# compass.net
KiCad netlist of a schematic drawn in EAGLE
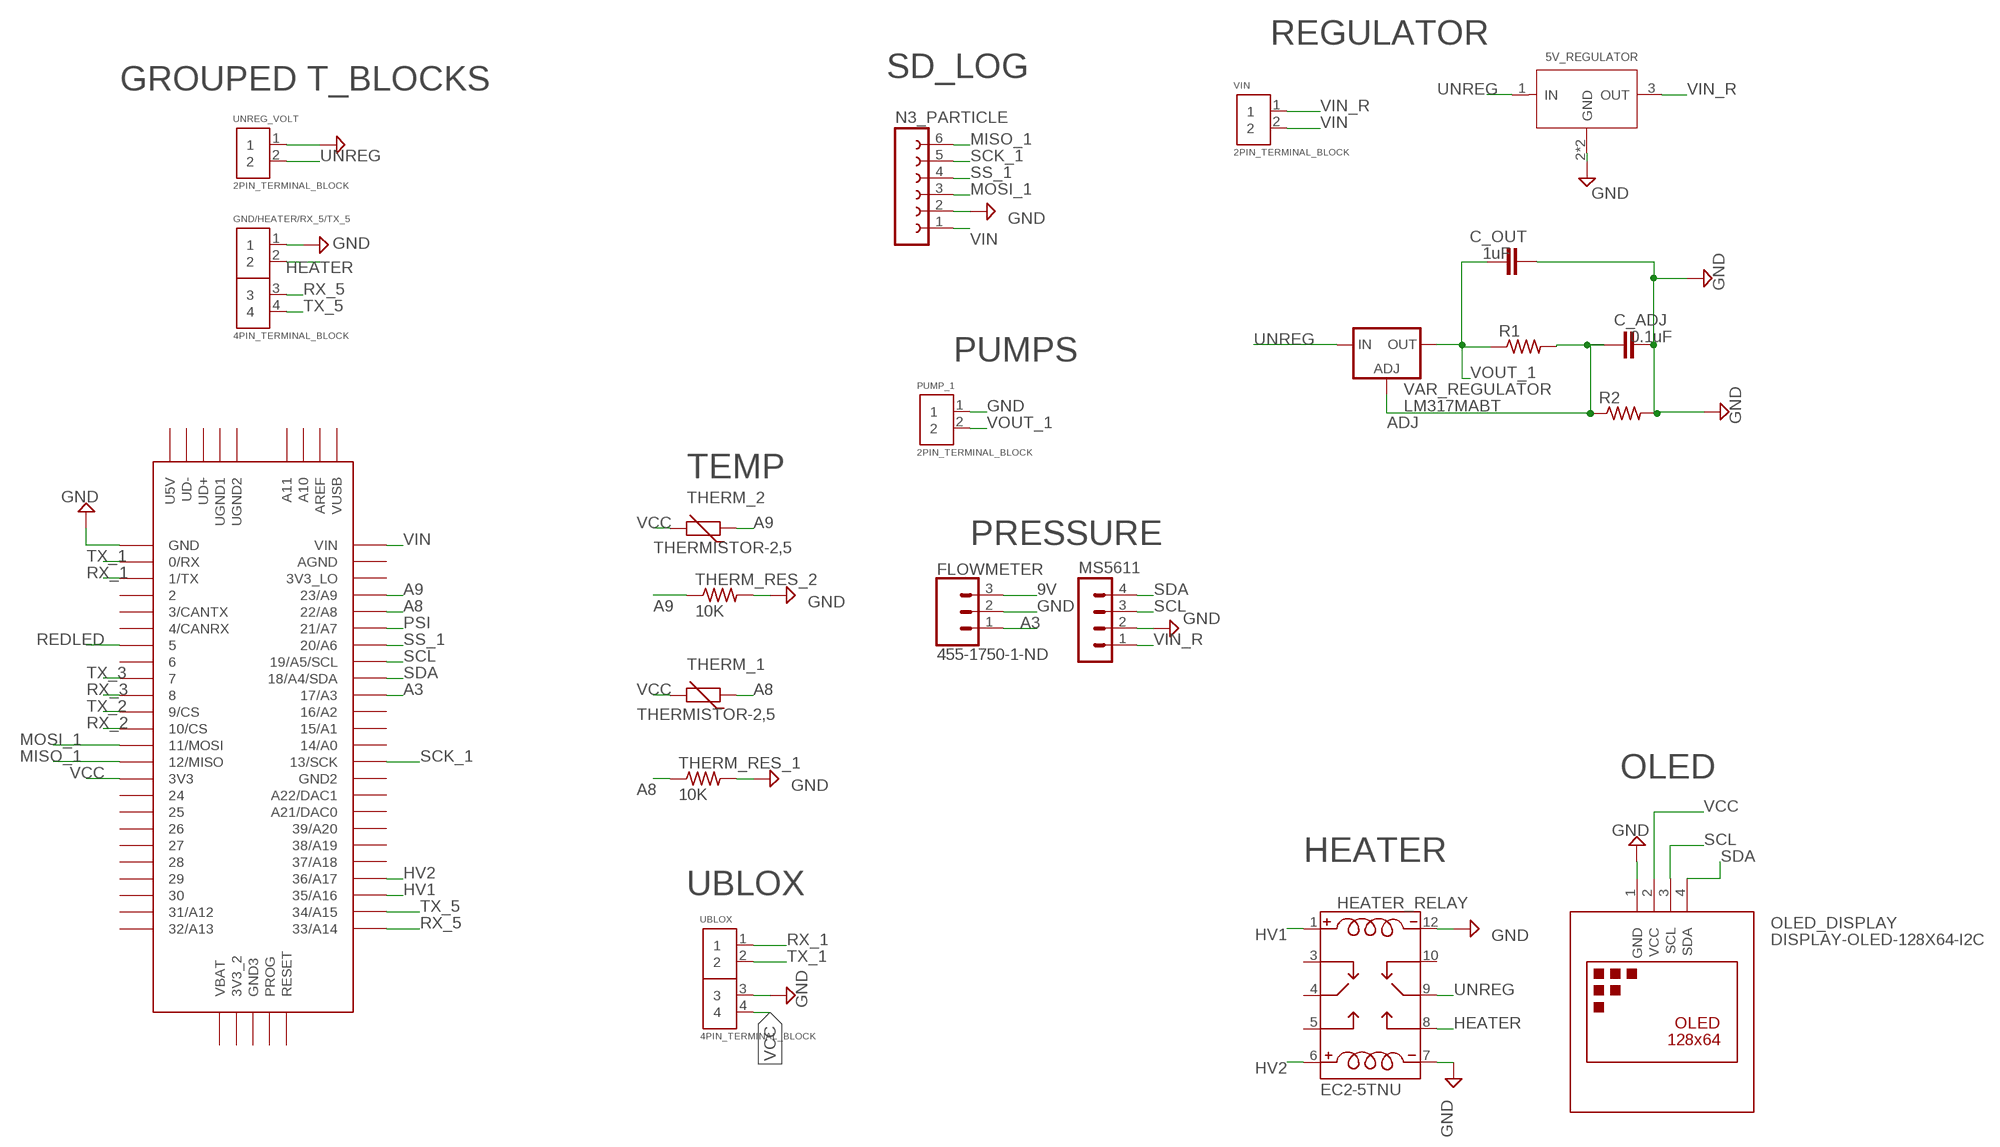
[diagram p0: schematic, sheet 1]

(export (version "E")
  (design (tool "Eeschema 10.0.6"))
  (components
    (comp (ref "5V_REGULATOR")
      (value "PMIC-L7805CV-DG(TO-220)")
      (footprint "eagle-import:TO-220")
      (fields
        (field (name "DIGI-KEY_PART_NUMBER") "497-12404-ND")
        (field (name "MF") "STMicroelectronics")
        (field (name "MP") "L7805CV-DG")
      )
      (libsource (lib "eagle-import") (part "PMIC-L7805CV-DG(TO-220)"))
    )
    (comp (ref "C_ADJ")
      (value "0.1uF")
      (footprint "eagle-import:C2.5-3")
      (libsource (lib "eagle-import") (part "C2,5-3"))
    )
    (comp (ref "C_OUT")
      (value "1uF")
      (footprint "eagle-import:C2.5-3")
      (libsource (lib "eagle-import") (part "C2,5-3"))
    )
    (comp (ref "FLOWMETER")
      (value "455-1750-1-ND")
      (footprint "eagle-import:1X03")
      (libsource (lib "eagle-import") (part "CONN_03"))
    )
    (comp (ref "GND/HEATER/RX_5/TX_5")
      (value "4PIN_TERMINAL_BLOCK")
      (footprint "eagle-import:4PIN_TERMINAL_BLOCK")
      (libsource (lib "eagle-import") (part "4PIN_TERMINAL_BLOCK"))
    )
    (comp (ref "HEATER_RELAY")
      (value "EC2-5TNU")
      (footprint "eagle-import:RELAY_EC2-5TNU")
      (fields (field (name "MF") "KEMET"))
      (libsource (lib "eagle-import") (part "EC2-5TNU"))
    )
    (comp (ref "MS5611")
      (value "MA04-1")
      (footprint "eagle-import:MA04-1")
      (libsource (lib "eagle-import") (part "MA04-1"))
    )
    (comp (ref "N3_PARTICLE")
      (value "FE06-1")
      (footprint "eagle-import:FE06")
      (libsource (lib "eagle-import") (part "FE06-1"))
    )
    (comp (ref "OLED_DISPLAY")
      (value "DISPLAY-OLED-128X64-I2C")
      (footprint "eagle-import:DISPLAY-OLED-128X64-I2C")
      (libsource (lib "eagle-import") (part "DISPLAY-OLED-128X64-I2C"))
    )
    (comp (ref "PUMP_1")
      (value "2PIN_TERMINAL_BLOCK")
      (footprint "eagle-import:2PIN_TERMINAL_BLOCK")
      (fields
        (field (name "COMMENT") "282834-2")
        (field (name "DIGI-KEY_PART_NUMBER") "A98333-ND")
        (field (name "MF") "TE Connectivity")
      )
      (libsource (lib "eagle-import") (part "2PIN_TERMINAL_BLOCK"))
    )
    (comp (ref "R1")
      (value "R-US_0204/7")
      (footprint "eagle-import:0204_7")
      (libsource (lib "eagle-import") (part "R-US_0204/7"))
    )
    (comp (ref "R2")
      (value "R-US_0204/7")
      (footprint "eagle-import:0204_7")
      (libsource (lib "eagle-import") (part "R-US_0204/7"))
    )
    (comp (ref "THERM_1")
      (value "THERMISTOR-2,5")
      (footprint "eagle-import:RS-2,5")
      (libsource (lib "eagle-import") (part "THERMISTOR-2,5"))
    )
    (comp (ref "THERM_2")
      (value "THERMISTOR-2,5")
      (footprint "eagle-import:RS-2,5")
      (libsource (lib "eagle-import") (part "THERMISTOR-2,5"))
    )
    (comp (ref "THERM_RES_1")
      (value "10K")
      (footprint "eagle-import:0204_7")
      (libsource (lib "eagle-import") (part "R-US_0204/7"))
    )
    (comp (ref "THERM_RES_2")
      (value "10K")
      (footprint "eagle-import:0204_7")
      (libsource (lib "eagle-import") (part "R-US_0204/7"))
    )
    (comp (ref "U$1")
      (value "TEENSY_3.5/3.6")
      (footprint "eagle-import:TEENSY_3.5_3.6")
      (libsource (lib "eagle-import") (part "TEENSY_3.5/3.6"))
    )
    (comp (ref "UBLOX")
      (value "4PIN_TERMINAL_BLOCK")
      (footprint "eagle-import:4PIN_TERMINAL_BLOCK")
      (libsource (lib "eagle-import") (part "4PIN_TERMINAL_BLOCK"))
    )
    (comp (ref "UNREG_VOLT")
      (value "2PIN_TERMINAL_BLOCK")
      (footprint "eagle-import:2PIN_TERMINAL_BLOCK")
      (fields
        (field (name "COMMENT") "282834-2")
        (field (name "DIGI-KEY_PART_NUMBER") "A98333-ND")
        (field (name "MF") "TE Connectivity")
      )
      (libsource (lib "eagle-import") (part "2PIN_TERMINAL_BLOCK"))
    )
    (comp (ref "VAR_REGULATOR")
      (value "LM317MABT")
      (footprint "eagle-import:TO220L1")
      (libsource (lib "eagle-import") (part "LM317?MABT"))
    )
    (comp (ref "VIN")
      (value "2PIN_TERMINAL_BLOCK")
      (footprint "eagle-import:2PIN_TERMINAL_BLOCK")
      (fields
        (field (name "COMMENT") "282834-2")
        (field (name "DIGI-KEY_PART_NUMBER") "A98333-ND")
        (field (name "MF") "TE Connectivity")
      )
      (libsource (lib "eagle-import") (part "2PIN_TERMINAL_BLOCK"))
    )
  )
  (nets
    (net (code "1") (name "/9V") (class "Default")
      (node (ref "FLOWMETER") (pin "3") (pinfunction "3_3") (pintype "passive"))
    )
    (net (code "2") (name "/A3") (class "Default")
      (node (ref "FLOWMETER") (pin "1") (pinfunction "1_1") (pintype "passive"))
      (node (ref "U$1") (pin "17/A3") (pinfunction "17/A3_17/A3") (pintype "bidirectional"))
    )
    (net (code "3") (name "/A8") (class "Default")
      (node (ref "THERM_1") (pin "1") (pinfunction "1_1") (pintype "passive"))
      (node (ref "THERM_RES_1") (pin "1") (pinfunction "1_1") (pintype "passive"))
      (node (ref "U$1") (pin "22/A8") (pinfunction "22/A8_22/A8") (pintype "bidirectional"))
    )
    (net (code "4") (name "/A9") (class "Default")
      (node (ref "THERM_2") (pin "1") (pinfunction "1_1") (pintype "passive"))
      (node (ref "THERM_RES_2") (pin "1") (pinfunction "1_1") (pintype "passive"))
      (node (ref "U$1") (pin "23/A9") (pinfunction "23/A9_23/A9") (pintype "bidirectional"))
    )
    (net (code "5") (name "/ADJ") (class "Default")
      (node (ref "C_ADJ") (pin "2") (pinfunction "2_2") (pintype "passive"))
      (node (ref "R1") (pin "2") (pinfunction "2_2") (pintype "passive"))
      (node (ref "R2") (pin "1") (pinfunction "1_1") (pintype "passive"))
      (node (ref "VAR_REGULATOR") (pin "1") (pinfunction "ADJ_1") (pintype "input"))
    )
    (net (code "6") (name "/HEATER") (class "Default")
      (node (ref "GND/HEATER/RX_5/TX_5") (pin "2") (pinfunction "2_2") (pintype "passive"))
      (node (ref "HEATER_RELAY") (pin "8") (pinfunction "NO_8") (pintype "passive"))
    )
    (net (code "7") (name "/HV1") (class "Default")
      (node (ref "HEATER_RELAY") (pin "1") (pinfunction "C1_1") (pintype "passive"))
      (node (ref "U$1") (pin "35/A16") (pinfunction "35/A16_35/A16") (pintype "bidirectional"))
    )
    (net (code "8") (name "/HV2") (class "Default")
      (node (ref "HEATER_RELAY") (pin "6") (pinfunction "C3_6") (pintype "passive"))
      (node (ref "U$1") (pin "36/A17") (pinfunction "36/A17_36/A17") (pintype "bidirectional"))
    )
    (net (code "9") (name "/MISO_1") (class "Default")
      (node (ref "N3_PARTICLE") (pin "6") (pinfunction "6_6") (pintype "passive"))
      (node (ref "U$1") (pin "12/MISO") (pinfunction "12/MISO_12/MISO") (pintype "bidirectional"))
    )
    (net (code "10") (name "/MOSI_1") (class "Default")
      (node (ref "N3_PARTICLE") (pin "3") (pinfunction "3_3") (pintype "passive"))
      (node (ref "U$1") (pin "11/MOSI") (pinfunction "11/MOSI_11/MOSI") (pintype "bidirectional"))
    )
    (net (code "11") (name "/PSI") (class "Default")
      (node (ref "U$1") (pin "21/A7") (pinfunction "21/A7_21/A7") (pintype "bidirectional"))
    )
    (net (code "12") (name "/REDLED") (class "Default")
      (node (ref "U$1") (pin "5") (pinfunction "5_5") (pintype "bidirectional"))
    )
    (net (code "13") (name "/RX_1") (class "Default")
      (node (ref "U$1") (pin "1/TX") (pinfunction "1/TX_1/TX") (pintype "bidirectional"))
      (node (ref "UBLOX") (pin "1") (pinfunction "1_1") (pintype "passive"))
    )
    (net (code "14") (name "/RX_2") (class "Default")
      (node (ref "U$1") (pin "10/CS") (pinfunction "10/CS_10/CS") (pintype "bidirectional"))
    )
    (net (code "15") (name "/RX_3") (class "Default")
      (node (ref "U$1") (pin "8") (pinfunction "8_8") (pintype "bidirectional"))
    )
    (net (code "16") (name "/RX_5") (class "Default")
      (node (ref "GND/HEATER/RX_5/TX_5") (pin "3") (pinfunction "3_3") (pintype "passive"))
      (node (ref "U$1") (pin "33/A14") (pinfunction "33/A14_33/A14") (pintype "bidirectional"))
    )
    (net (code "17") (name "/SCK_1") (class "Default")
      (node (ref "N3_PARTICLE") (pin "5") (pinfunction "5_5") (pintype "passive"))
      (node (ref "U$1") (pin "13/SCK") (pinfunction "13/SCK_13/SCK") (pintype "bidirectional"))
    )
    (net (code "18") (name "/SCL") (class "Default")
      (node (ref "MS5611") (pin "3") (pinfunction "3_3") (pintype "passive"))
      (node (ref "OLED_DISPLAY") (pin "3") (pinfunction "SCL_3") (pintype "bidirectional"))
      (node (ref "U$1") (pin "19/A5/SCL") (pinfunction "19/A5/SCL_19/A5/SCL") (pintype "bidirectional"))
    )
    (net (code "19") (name "/SDA") (class "Default")
      (node (ref "MS5611") (pin "4") (pinfunction "4_4") (pintype "passive"))
      (node (ref "OLED_DISPLAY") (pin "4") (pinfunction "SDA_4") (pintype "bidirectional"))
      (node (ref "U$1") (pin "18/A4/SDA") (pinfunction "18/A4/SDA_18/A4/SDA") (pintype "bidirectional"))
    )
    (net (code "20") (name "/SS_1") (class "Default")
      (node (ref "N3_PARTICLE") (pin "4") (pinfunction "4_4") (pintype "passive"))
      (node (ref "U$1") (pin "20/A6") (pinfunction "20/A6_20/A6") (pintype "bidirectional"))
    )
    (net (code "21") (name "/TX_1") (class "Default")
      (node (ref "U$1") (pin "0/RX") (pinfunction "0/RX_0/RX") (pintype "bidirectional"))
      (node (ref "UBLOX") (pin "2") (pinfunction "2_2") (pintype "passive"))
    )
    (net (code "22") (name "/TX_2") (class "Default")
      (node (ref "U$1") (pin "9/CS") (pinfunction "9/CS_9/CS") (pintype "bidirectional"))
    )
    (net (code "23") (name "/TX_3") (class "Default")
      (node (ref "U$1") (pin "7") (pinfunction "7_7") (pintype "bidirectional"))
    )
    (net (code "24") (name "/TX_5") (class "Default")
      (node (ref "GND/HEATER/RX_5/TX_5") (pin "4") (pinfunction "4_4") (pintype "passive"))
      (node (ref "U$1") (pin "34/A15") (pinfunction "34/A15_34/A15") (pintype "bidirectional"))
    )
    (net (code "25") (name "/UNREG") (class "Default")
      (node (ref "5V_REGULATOR") (pin "1") (pinfunction "IN_1") (pintype "bidirectional"))
      (node (ref "HEATER_RELAY") (pin "9") (pinfunction "M_9") (pintype "passive"))
      (node (ref "UNREG_VOLT") (pin "2") (pinfunction "2_2") (pintype "passive"))
      (node (ref "VAR_REGULATOR") (pin "3") (pinfunction "IN_3") (pintype "input"))
    )
    (net (code "26") (name "/VIN") (class "Default")
      (node (ref "N3_PARTICLE") (pin "1") (pinfunction "1_1") (pintype "passive"))
      (node (ref "U$1") (pin "VIN") (pinfunction "VIN_VIN") (pintype "bidirectional"))
      (node (ref "VIN") (pin "2") (pinfunction "2_2") (pintype "passive"))
    )
    (net (code "27") (name "/VIN_R") (class "Default")
      (node (ref "5V_REGULATOR") (pin "3") (pinfunction "OUT_3") (pintype "bidirectional"))
      (node (ref "MS5611") (pin "1") (pinfunction "1_1") (pintype "passive"))
      (node (ref "VIN") (pin "1") (pinfunction "1_1") (pintype "passive"))
    )
    (net (code "28") (name "/VOUT_1") (class "Default")
      (node (ref "C_OUT") (pin "1") (pinfunction "1_1") (pintype "passive"))
      (node (ref "PUMP_1") (pin "2") (pinfunction "2_2") (pintype "passive"))
      (node (ref "R1") (pin "1") (pinfunction "1_1") (pintype "passive"))
      (node (ref "VAR_REGULATOR") (pin "2") (pinfunction "OUT_2") (pintype "passive"))
    )
    (net (code "29") (name "GND") (class "Default")
      (node (ref "5V_REGULATOR") (pin "2") (pinfunction "GND_2") (pintype "bidirectional"))
      (node (ref "5V_REGULATOR") (pin "HEAT") (pinfunction "GND_HEAT") (pintype "bidirectional"))
      (node (ref "C_ADJ") (pin "1") (pinfunction "1_1") (pintype "passive"))
      (node (ref "C_OUT") (pin "2") (pinfunction "2_2") (pintype "passive"))
      (node (ref "FLOWMETER") (pin "2") (pinfunction "2_2") (pintype "passive"))
      (node (ref "GND/HEATER/RX_5/TX_5") (pin "1") (pinfunction "1_1") (pintype "passive"))
      (node (ref "HEATER_RELAY") (pin "12") (pinfunction "C2_12") (pintype "passive"))
      (node (ref "HEATER_RELAY") (pin "7") (pinfunction "C4_7") (pintype "passive"))
      (node (ref "MS5611") (pin "2") (pinfunction "2_2") (pintype "passive"))
      (node (ref "N3_PARTICLE") (pin "2") (pinfunction "2_2") (pintype "passive"))
      (node (ref "OLED_DISPLAY") (pin "1") (pinfunction "GND_1") (pintype "power_in"))
      (node (ref "PUMP_1") (pin "1") (pinfunction "1_1") (pintype "passive"))
      (node (ref "R2") (pin "2") (pinfunction "2_2") (pintype "passive"))
      (node (ref "THERM_RES_1") (pin "2") (pinfunction "2_2") (pintype "passive"))
      (node (ref "THERM_RES_2") (pin "2") (pinfunction "2_2") (pintype "passive"))
      (node (ref "U$1") (pin "GND") (pinfunction "GND_GND") (pintype "bidirectional"))
      (node (ref "UBLOX") (pin "3") (pinfunction "3_3") (pintype "passive"))
      (node (ref "UNREG_VOLT") (pin "1") (pinfunction "1_1") (pintype "passive"))
    )
    (net (code "30") (name "VCC") (class "Default")
      (node (ref "OLED_DISPLAY") (pin "2") (pinfunction "VCC_2") (pintype "power_in"))
      (node (ref "THERM_1") (pin "2") (pinfunction "2_2") (pintype "passive"))
      (node (ref "THERM_2") (pin "2") (pinfunction "2_2") (pintype "passive"))
      (node (ref "U$1") (pin "3V3") (pinfunction "3V3_3V3") (pintype "bidirectional"))
      (node (ref "UBLOX") (pin "4") (pinfunction "4_4") (pintype "passive"))
    )
    (net (code "31") (name "unconnected-(HEATER_RELAY-M1-Pad4)") (class "Default")
      (node (ref "HEATER_RELAY") (pin "4") (pinfunction "M1_4") (pintype "passive"))
    )
    (net (code "32") (name "unconnected-(HEATER_RELAY-NC-Pad10)") (class "Default")
      (node (ref "HEATER_RELAY") (pin "10") (pinfunction "NC_10") (pintype "passive"))
    )
    (net (code "33") (name "unconnected-(HEATER_RELAY-NC1-Pad3)") (class "Default")
      (node (ref "HEATER_RELAY") (pin "3") (pinfunction "NC1_3") (pintype "passive"))
    )
    (net (code "34") (name "unconnected-(HEATER_RELAY-NO1-Pad5)") (class "Default")
      (node (ref "HEATER_RELAY") (pin "5") (pinfunction "NO1_5") (pintype "passive"))
    )
    (net (code "35") (name "unconnected-(U$1-A21{slash}DAC0-Pad21{slash}DAC0)") (class "Default")
      (node (ref "U$1") (pin "21/DAC0") (pinfunction "A21/DAC0_21/DAC0") (pintype "bidirectional"))
    )
    (net (code "36") (name "unconnected-(U$1-Pad2)") (class "Default")
      (node (ref "U$1") (pin "2") (pinfunction "2_2") (pintype "bidirectional"))
    )
    (net (code "37") (name "unconnected-(U$1-Pad3V3_2)") (class "Default")
      (node (ref "U$1") (pin "3V3_2") (pinfunction "3V3_2_3V3_2") (pintype "bidirectional"))
    )
    (net (code "38") (name "unconnected-(U$1-Pad3V3_LO)") (class "Default")
      (node (ref "U$1") (pin "3V3_LO") (pinfunction "3V3_LO_3V3_LO") (pintype "bidirectional"))
    )
    (net (code "39") (name "unconnected-(U$1-Pad3{slash}CANTX)") (class "Default")
      (node (ref "U$1") (pin "3/CANTX") (pinfunction "3/CANTX_3/CANTX") (pintype "bidirectional"))
    )
    (net (code "40") (name "unconnected-(U$1-Pad4{slash}CANRX)") (class "Default")
      (node (ref "U$1") (pin "4/CANRX") (pinfunction "4/CANRX_4/CANRX") (pintype "bidirectional"))
    )
    (net (code "41") (name "unconnected-(U$1-Pad6)") (class "Default")
      (node (ref "U$1") (pin "6") (pinfunction "6_6") (pintype "bidirectional"))
    )
    (net (code "42") (name "unconnected-(U$1-Pad14{slash}A0)") (class "Default")
      (node (ref "U$1") (pin "14/A0") (pinfunction "14/A0_14/A0") (pintype "bidirectional"))
    )
    (net (code "43") (name "unconnected-(U$1-Pad15{slash}A1)") (class "Default")
      (node (ref "U$1") (pin "15/A1") (pinfunction "15/A1_15/A1") (pintype "bidirectional"))
    )
    (net (code "44") (name "unconnected-(U$1-Pad16{slash}A2)") (class "Default")
      (node (ref "U$1") (pin "16/A2") (pinfunction "16/A2_16/A2") (pintype "bidirectional"))
    )
    (net (code "45") (name "unconnected-(U$1-Pad24)") (class "Default")
      (node (ref "U$1") (pin "24") (pinfunction "24_24") (pintype "bidirectional"))
    )
    (net (code "46") (name "unconnected-(U$1-Pad25)") (class "Default")
      (node (ref "U$1") (pin "25") (pinfunction "25_25") (pintype "bidirectional"))
    )
    (net (code "47") (name "unconnected-(U$1-Pad26)") (class "Default")
      (node (ref "U$1") (pin "26") (pinfunction "26_26") (pintype "bidirectional"))
    )
    (net (code "48") (name "unconnected-(U$1-Pad27)") (class "Default")
      (node (ref "U$1") (pin "27") (pinfunction "27_27") (pintype "bidirectional"))
    )
    (net (code "49") (name "unconnected-(U$1-Pad28)") (class "Default")
      (node (ref "U$1") (pin "28") (pinfunction "28_28") (pintype "bidirectional"))
    )
    (net (code "50") (name "unconnected-(U$1-Pad29)") (class "Default")
      (node (ref "U$1") (pin "29") (pinfunction "29_29") (pintype "bidirectional"))
    )
    (net (code "51") (name "unconnected-(U$1-Pad30)") (class "Default")
      (node (ref "U$1") (pin "30") (pinfunction "30_30") (pintype "bidirectional"))
    )
    (net (code "52") (name "unconnected-(U$1-Pad31{slash}A12)") (class "Default")
      (node (ref "U$1") (pin "31/A12") (pinfunction "31/A12_31/A12") (pintype "bidirectional"))
    )
    (net (code "53") (name "unconnected-(U$1-Pad32{slash}A13)") (class "Default")
      (node (ref "U$1") (pin "32/A13") (pinfunction "32/A13_32/A13") (pintype "bidirectional"))
    )
    (net (code "54") (name "unconnected-(U$1-Pad37{slash}A18)") (class "Default")
      (node (ref "U$1") (pin "37/A18") (pinfunction "37/A18_37/A18") (pintype "bidirectional"))
    )
    (net (code "55") (name "unconnected-(U$1-Pad38{slash}A19)") (class "Default")
      (node (ref "U$1") (pin "38/A19") (pinfunction "38/A19_38/A19") (pintype "bidirectional"))
    )
    (net (code "56") (name "unconnected-(U$1-Pad39{slash}A20)") (class "Default")
      (node (ref "U$1") (pin "39/A20") (pinfunction "39/A20_39/A20") (pintype "bidirectional"))
    )
    (net (code "57") (name "unconnected-(U$1-PadA10)") (class "Default")
      (node (ref "U$1") (pin "A10") (pinfunction "A10_A10") (pintype "bidirectional"))
    )
    (net (code "58") (name "unconnected-(U$1-PadA11)") (class "Default")
      (node (ref "U$1") (pin "A11") (pinfunction "A11_A11") (pintype "bidirectional"))
    )
    (net (code "59") (name "unconnected-(U$1-PadA22{slash}DAC1)") (class "Default")
      (node (ref "U$1") (pin "A22/DAC1") (pinfunction "A22/DAC1_A22/DAC1") (pintype "bidirectional"))
    )
    (net (code "60") (name "unconnected-(U$1-PadAGND)") (class "Default")
      (node (ref "U$1") (pin "AGND") (pinfunction "AGND_AGND") (pintype "bidirectional"))
    )
    (net (code "61") (name "unconnected-(U$1-PadAREF)") (class "Default")
      (node (ref "U$1") (pin "AREF") (pinfunction "AREF_AREF") (pintype "bidirectional"))
    )
    (net (code "62") (name "unconnected-(U$1-PadGND2)") (class "Default")
      (node (ref "U$1") (pin "GND2") (pinfunction "GND2_GND2") (pintype "bidirectional"))
    )
    (net (code "63") (name "unconnected-(U$1-PadGND3)") (class "Default")
      (node (ref "U$1") (pin "GND3") (pinfunction "GND3_GND3") (pintype "bidirectional"))
    )
    (net (code "64") (name "unconnected-(U$1-PadPROG)") (class "Default")
      (node (ref "U$1") (pin "PROG") (pinfunction "PROG_PROG") (pintype "bidirectional"))
    )
    (net (code "65") (name "unconnected-(U$1-PadRESET)") (class "Default")
      (node (ref "U$1") (pin "RESET") (pinfunction "RESET_RESET") (pintype "bidirectional"))
    )
    (net (code "66") (name "unconnected-(U$1-PadU5V)") (class "Default")
      (node (ref "U$1") (pin "U5V") (pinfunction "U5V_U5V") (pintype "bidirectional"))
    )
    (net (code "67") (name "unconnected-(U$1-PadUD+)") (class "Default")
      (node (ref "U$1") (pin "UD+") (pinfunction "UD+_UD+") (pintype "bidirectional"))
    )
    (net (code "68") (name "unconnected-(U$1-PadUD-)") (class "Default")
      (node (ref "U$1") (pin "UD-") (pinfunction "UD-_UD-") (pintype "bidirectional"))
    )
    (net (code "69") (name "unconnected-(U$1-PadUGND1)") (class "Default")
      (node (ref "U$1") (pin "UGND1") (pinfunction "UGND1_UGND1") (pintype "bidirectional"))
    )
    (net (code "70") (name "unconnected-(U$1-PadUGND2)") (class "Default")
      (node (ref "U$1") (pin "UGND2") (pinfunction "UGND2_UGND2") (pintype "bidirectional"))
    )
    (net (code "71") (name "unconnected-(U$1-PadVBAT)") (class "Default")
      (node (ref "U$1") (pin "VBAT") (pinfunction "VBAT_VBAT") (pintype "bidirectional"))
    )
    (net (code "72") (name "unconnected-(U$1-PadVUSB)") (class "Default")
      (node (ref "U$1") (pin "VUSB") (pinfunction "VUSB_VUSB") (pintype "bidirectional"))
    )
  )
)
